# SCH_USB-turtle_2024-06-30_1.net
KiCad netlist of a schematic drawn in EasyEDA
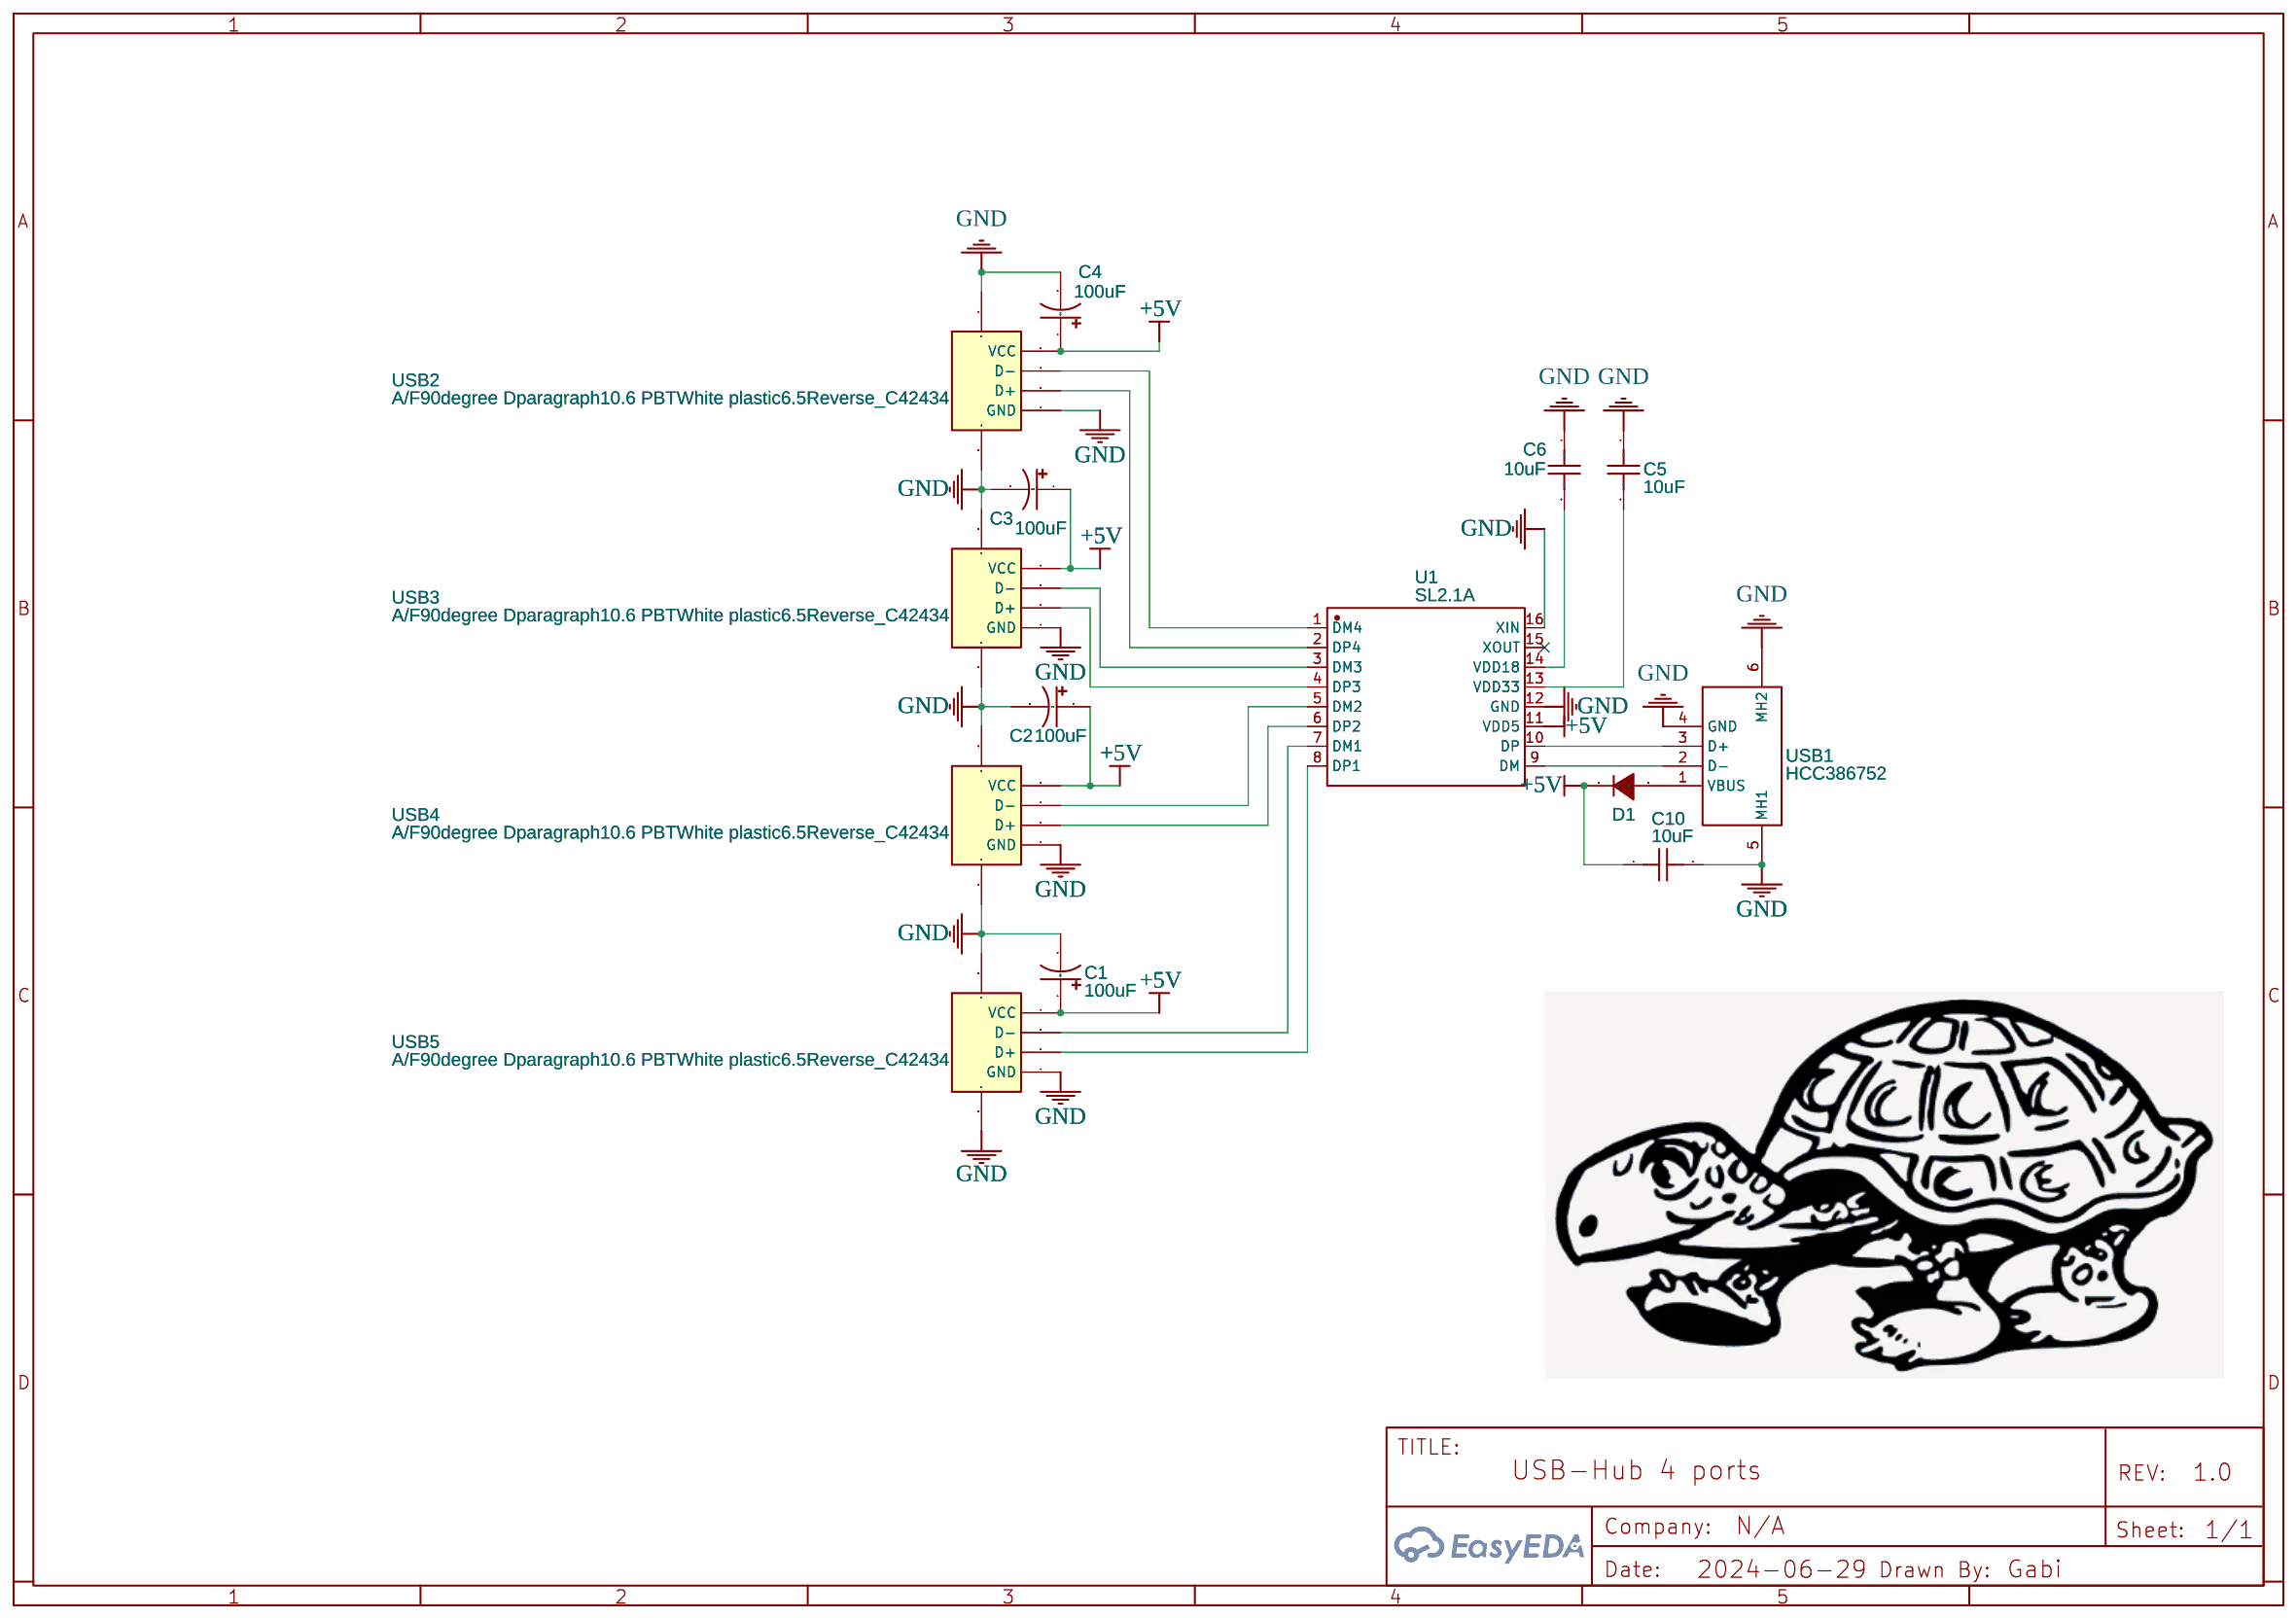
[diagram p0: schematic sheet]

(export (version "E")
  (design (tool "Eeschema 10.0.6"))
  (components
    (comp (ref "C1")
      (value "100uF")
      (fields
        (field (name "Manufacturer Part") "NXB16V100M5*11 LO")
        (field (name "Manufacturer") "SAMYOUNG(韩国三莹)")
      )
      (libsource (lib "") (part "NXB16VB100M5*11_LO_1"))
    )
    (comp (ref "C2")
      (value "100uF")
      (fields
        (field (name "Manufacturer Part") "NXB16V100M5*11 LO")
        (field (name "Manufacturer") "SAMYOUNG(韩国三莹)")
      )
      (libsource (lib "") (part "NXB16VB100M5*11_LO"))
    )
    (comp (ref "C3")
      (value "100uF")
      (fields
        (field (name "Manufacturer Part") "NXB16V100M5*11 LO")
        (field (name "Manufacturer") "SAMYOUNG(韩国三莹)")
      )
      (libsource (lib "") (part "NXB16VB100M5*11_LO"))
    )
    (comp (ref "C4")
      (value "100uF")
      (fields
        (field (name "Manufacturer Part") "NXB16V100M5*11 LO")
        (field (name "Manufacturer") "SAMYOUNG(韩国三莹)")
      )
      (libsource (lib "") (part "NXB16VB100M5*11_LO_1"))
    )
    (comp (ref "C5")
      (value "10uF")
      (fields (field (name "Manufacturer Part") "C1608JB0J106M080AB") (field (name "Manufacturer") "TDK"))
      (libsource (lib "") (part "C1608JB0J106M080AB"))
    )
    (comp (ref "C6")
      (value "10uF")
      (fields (field (name "Manufacturer Part") "C1608JB0J106M080AB") (field (name "Manufacturer") "TDK"))
      (libsource (lib "") (part "C1608JB0J106M080AB"))
    )
    (comp (ref "C10")
      (value "10uF")
      (fields (field (name "Manufacturer Part") "C1608JB0J106M080AB") (field (name "Manufacturer") "TDK"))
      (libsource (lib "") (part "C1608JB0J106M080AB_1"))
    )
    (comp (ref "D1")
      (value "NSR0320MW2T1G")
      (fields (field (name "Manufacturer") "onsemi(安森美)"))
      (libsource (lib "") (part "NSR0320MW2T1G"))
    )
    (comp (ref "U1")
      (value "SL2.1A")
      (fields (field (name "Manufacturer") "CoreChips(和芯润德)"))
      (libsource (lib "") (part "SL2.1A"))
    )
    (comp (ref "USB1")
      (value "HCC386752")
      (fields (field (name "Manufacturer Part") "U-USBAR04P-M003") (field (name "Manufacturer") "Ckmtw(灿科盟)"))
      (libsource (lib "") (part "HCC386752"))
    )
    (comp (ref "USB2")
      (value "A/F90degree Dparagraph10.6 PBTWhite plastic6.5Reverse_C42434")
      (fields
        (field (name "Manufacturer Part") "A/F90度 D款10.6后两脚无卷边铜壳PBT白胶6.5反向")
        (field (name "Manufacturer") "精拓金")
      )
      (libsource (lib "") (part "A/F90degree Dparagraph10.6 PBTWhite plastic6.5Reverse_C42434"))
    )
    (comp (ref "USB3")
      (value "A/F90degree Dparagraph10.6 PBTWhite plastic6.5Reverse_C42434")
      (fields
        (field (name "Manufacturer Part") "A/F90度 D款10.6后两脚无卷边铜壳PBT白胶6.5反向")
        (field (name "Manufacturer") "精拓金")
      )
      (libsource (lib "") (part "A/F90degree Dparagraph10.6 PBTWhite plastic6.5Reverse_C42434"))
    )
    (comp (ref "USB4")
      (value "A/F90degree Dparagraph10.6 PBTWhite plastic6.5Reverse_C42434")
      (fields
        (field (name "Manufacturer Part") "A/F90度 D款10.6后两脚无卷边铜壳PBT白胶6.5反向")
        (field (name "Manufacturer") "精拓金")
      )
      (libsource (lib "") (part "A/F90degree Dparagraph10.6 PBTWhite plastic6.5Reverse_C42434"))
    )
    (comp (ref "USB5")
      (value "A/F90degree Dparagraph10.6 PBTWhite plastic6.5Reverse_C42434")
      (fields
        (field (name "Manufacturer Part") "A/F90度 D款10.6后两脚无卷边铜壳PBT白胶6.5反向")
        (field (name "Manufacturer") "精拓金")
      )
      (libsource (lib "") (part "A/F90degree Dparagraph10.6 PBTWhite plastic6.5Reverse_C42434"))
    )
  )
  (nets
    (net (code "1") (name "+5V") (class "Default")
      (node (ref "C1") (pin "1") (pinfunction "1_1") (pintype "unspecified"))
      (node (ref "C10") (pin "1") (pinfunction "1_1") (pintype "unspecified"))
      (node (ref "C2") (pin "1") (pinfunction "1_1") (pintype "unspecified"))
      (node (ref "C3") (pin "1") (pinfunction "1_1") (pintype "unspecified"))
      (node (ref "C4") (pin "1") (pinfunction "1_1") (pintype "unspecified"))
      (node (ref "D1") (pin "1") (pinfunction "C_1") (pintype "unspecified"))
      (node (ref "U1") (pin "11") (pinfunction "VDD5_11") (pintype "unspecified"))
      (node (ref "USB2") (pin "1") (pinfunction "VCC_1") (pintype "input"))
      (node (ref "USB3") (pin "1") (pinfunction "VCC_1") (pintype "input"))
      (node (ref "USB4") (pin "1") (pinfunction "VCC_1") (pintype "input"))
      (node (ref "USB5") (pin "1") (pinfunction "VCC_1") (pintype "input"))
    )
    (net (code "2") (name "GND") (class "Default")
      (node (ref "C1") (pin "2") (pinfunction "2_2") (pintype "unspecified"))
      (node (ref "C10") (pin "2") (pinfunction "2_2") (pintype "unspecified"))
      (node (ref "C2") (pin "2") (pinfunction "2_2") (pintype "unspecified"))
      (node (ref "C3") (pin "2") (pinfunction "2_2") (pintype "unspecified"))
      (node (ref "C4") (pin "2") (pinfunction "2_2") (pintype "unspecified"))
      (node (ref "C5") (pin "1") (pinfunction "1_1") (pintype "unspecified"))
      (node (ref "C6") (pin "1") (pinfunction "1_1") (pintype "unspecified"))
      (node (ref "U1") (pin "12") (pinfunction "GND_12") (pintype "unspecified"))
      (node (ref "U1") (pin "16") (pinfunction "XIN_16") (pintype "unspecified"))
      (node (ref "USB1") (pin "4") (pinfunction "GND_4") (pintype "unspecified"))
      (node (ref "USB1") (pin "5") (pinfunction "MH1_5") (pintype "unspecified"))
      (node (ref "USB1") (pin "6") (pinfunction "MH2_6") (pintype "unspecified"))
      (node (ref "USB2") (pin "0") (pinfunction "0_0") (pintype "unspecified"))
      (node (ref "USB2") (pin "4") (pinfunction "GND_4") (pintype "input"))
      (node (ref "USB3") (pin "0") (pinfunction "0_0") (pintype "unspecified"))
      (node (ref "USB3") (pin "4") (pinfunction "GND_4") (pintype "input"))
      (node (ref "USB4") (pin "0") (pinfunction "0_0") (pintype "unspecified"))
      (node (ref "USB4") (pin "4") (pinfunction "GND_4") (pintype "input"))
      (node (ref "USB5") (pin "0") (pinfunction "0_0") (pintype "unspecified"))
      (node (ref "USB5") (pin "4") (pinfunction "GND_4") (pintype "input"))
    )
    (net (code "3") (name "Net-(D1-A)") (class "Default")
      (node (ref "D1") (pin "2") (pinfunction "A_2") (pintype "unspecified"))
      (node (ref "USB1") (pin "1") (pinfunction "VBUS_1") (pintype "unspecified"))
    )
    (net (code "4") (name "Net-(U1-DM)") (class "Default")
      (node (ref "U1") (pin "9") (pinfunction "DM_9") (pintype "unspecified"))
      (node (ref "USB1") (pin "2") (pinfunction "D-_2") (pintype "unspecified"))
    )
    (net (code "5") (name "Net-(U1-DM1)") (class "Default")
      (node (ref "U1") (pin "7") (pinfunction "DM1_7") (pintype "unspecified"))
      (node (ref "USB5") (pin "2") (pinfunction "D-_2") (pintype "input"))
    )
    (net (code "6") (name "Net-(U1-DM2)") (class "Default")
      (node (ref "U1") (pin "5") (pinfunction "DM2_5") (pintype "unspecified"))
      (node (ref "USB4") (pin "2") (pinfunction "D-_2") (pintype "input"))
    )
    (net (code "7") (name "Net-(U1-DM3)") (class "Default")
      (node (ref "U1") (pin "3") (pinfunction "DM3_3") (pintype "unspecified"))
      (node (ref "USB3") (pin "2") (pinfunction "D-_2") (pintype "input"))
    )
    (net (code "8") (name "Net-(U1-DM4)") (class "Default")
      (node (ref "U1") (pin "1") (pinfunction "DM4_1") (pintype "unspecified"))
      (node (ref "USB2") (pin "2") (pinfunction "D-_2") (pintype "input"))
    )
    (net (code "9") (name "Net-(U1-DP)") (class "Default")
      (node (ref "U1") (pin "10") (pinfunction "DP_10") (pintype "unspecified"))
      (node (ref "USB1") (pin "3") (pinfunction "D+_3") (pintype "unspecified"))
    )
    (net (code "10") (name "Net-(U1-DP1)") (class "Default")
      (node (ref "U1") (pin "8") (pinfunction "DP1_8") (pintype "unspecified"))
      (node (ref "USB5") (pin "3") (pinfunction "D+_3") (pintype "input"))
    )
    (net (code "11") (name "Net-(U1-DP2)") (class "Default")
      (node (ref "U1") (pin "6") (pinfunction "DP2_6") (pintype "unspecified"))
      (node (ref "USB4") (pin "3") (pinfunction "D+_3") (pintype "input"))
    )
    (net (code "12") (name "Net-(U1-DP3)") (class "Default")
      (node (ref "U1") (pin "4") (pinfunction "DP3_4") (pintype "unspecified"))
      (node (ref "USB3") (pin "3") (pinfunction "D+_3") (pintype "input"))
    )
    (net (code "13") (name "Net-(U1-DP4)") (class "Default")
      (node (ref "U1") (pin "2") (pinfunction "DP4_2") (pintype "unspecified"))
      (node (ref "USB2") (pin "3") (pinfunction "D+_3") (pintype "input"))
    )
    (net (code "14") (name "Net-(U1-VDD18)") (class "Default")
      (node (ref "C6") (pin "2") (pinfunction "2_2") (pintype "unspecified"))
      (node (ref "U1") (pin "14") (pinfunction "VDD18_14") (pintype "unspecified"))
    )
    (net (code "15") (name "Net-(U1-VDD33)") (class "Default")
      (node (ref "C5") (pin "2") (pinfunction "2_2") (pintype "unspecified"))
      (node (ref "U1") (pin "13") (pinfunction "VDD33_13") (pintype "unspecified"))
    )
    (net (code "16") (name "unconnected-(U1-XOUT-Pad15)") (class "Default")
      (node (ref "U1") (pin "15") (pinfunction "XOUT_15") (pintype "unspecified+no_connect"))
    )
  )
)
